# BatteryRegulators.net
KiCad netlist of a schematic drawn in Altium Designer
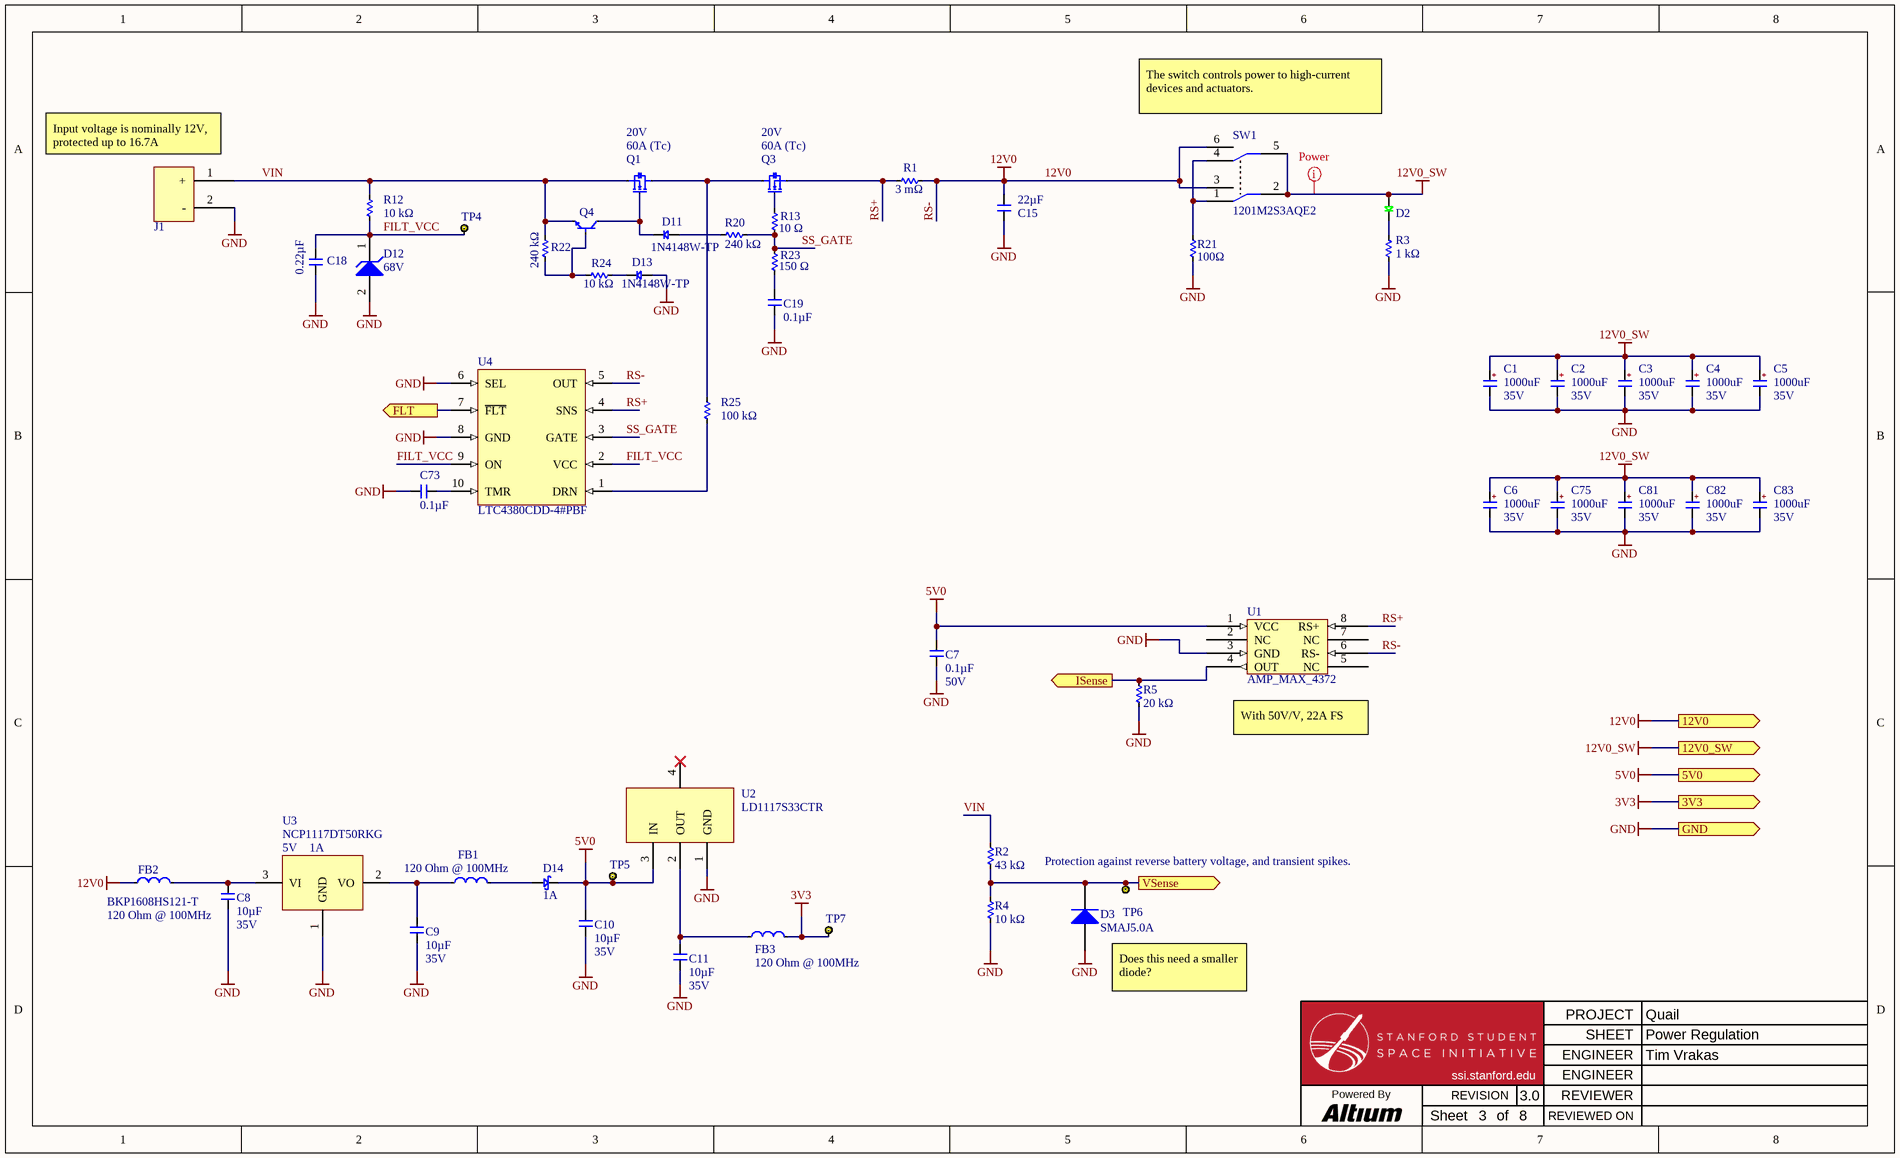
[diagram p0: BatteryRegulators.SchDoc]

(export (version "E")
  (design (tool "Eeschema 10.0.6"))
  (components
    (comp (ref "C1")
      (value "1000uF")
      (footprint "ALUM_CAP_5mm-Leads")
      (description "1000uF (1mF) Electrolytic Capacitor in a 12.5mm x 20mm can package")
      (fields (field (name "RATING") "35V") (field (name "Comment") "CAP_ALUM_1000uF_ECA-1VM102B"))
      (libsource (lib "Stanford Student Space Initiative") (part "CAP_ALUM_1000uF_ECA-1VM102B"))
    )
    (comp (ref "C2")
      (value "1000uF")
      (footprint "ALUM_CAP_5mm-Leads")
      (description "1000uF (1mF) Electrolytic Capacitor in a 12.5mm x 20mm can package")
      (fields (field (name "RATING") "35V") (field (name "Comment") "CAP_ALUM_1000uF_ECA-1VM102B"))
      (libsource (lib "Stanford Student Space Initiative") (part "CAP_ALUM_1000uF_ECA-1VM102B"))
    )
    (comp (ref "C3")
      (value "1000uF")
      (footprint "ALUM_CAP_5mm-Leads")
      (description "1000uF (1mF) Electrolytic Capacitor in a 12.5mm x 20mm can package")
      (fields (field (name "RATING") "35V") (field (name "Comment") "CAP_ALUM_1000uF_ECA-1VM102B"))
      (libsource (lib "Stanford Student Space Initiative") (part "CAP_ALUM_1000uF_ECA-1VM102B"))
    )
    (comp (ref "C4")
      (value "1000uF")
      (footprint "ALUM_CAP_5mm-Leads")
      (description "1000uF (1mF) Electrolytic Capacitor in a 12.5mm x 20mm can package")
      (fields (field (name "RATING") "35V") (field (name "Comment") "CAP_ALUM_1000uF_ECA-1VM102B"))
      (libsource (lib "Stanford Student Space Initiative") (part "CAP_ALUM_1000uF_ECA-1VM102B"))
    )
    (comp (ref "C5")
      (value "1000uF")
      (footprint "ALUM_CAP_5mm-Leads")
      (description "1000uF (1mF) Electrolytic Capacitor in a 12.5mm x 20mm can package")
      (fields (field (name "RATING") "35V") (field (name "Comment") "CAP_ALUM_1000uF_ECA-1VM102B"))
      (libsource (lib "Stanford Student Space Initiative") (part "CAP_ALUM_1000uF_ECA-1VM102B"))
    )
    (comp (ref "C6")
      (value "1000uF")
      (footprint "ALUM_CAP_5mm-Leads")
      (description "1000uF (1mF) Electrolytic Capacitor in a 12.5mm x 20mm can package")
      (fields (field (name "RATING") "35V") (field (name "Comment") "CAP_ALUM_1000uF_ECA-1VM102B"))
      (libsource (lib "Stanford Student Space Initiative") (part "CAP_ALUM_1000uF_ECA-1VM102B"))
    )
    (comp (ref "C7")
      (value "490-1519-1-ND")
      (footprint "C0603")
      (description "CAP CER 0603 0.1µF X7R 50V 10%")
      (fields
        (field (name "CAPACITANCE (SHORTHAND)") "0.1µF")
        (field (name "RATED VOLTAGE") "50V")
        (field (name "MANUFACTURER") "Murata Electronics North America")
      )
      (libsource (lib "Stanford Student Space Initiative") (part "__template_cap"))
    )
    (comp (ref "C8")
      (value "490-13248-1-ND")
      (footprint "C0603")
      (description "CAP CER 10UF 35V X5R 0603 20%")
      (fields
        (field (name "CAPACITANCE (SHORTHAND)") "10µF")
        (field (name "RATED VOLTAGE") "35V")
        (field (name "MANUFACTURER") "Murata Electronics North America")
      )
      (libsource (lib "Stanford Student Space Initiative") (part "__template_cap"))
    )
    (comp (ref "C9")
      (value "490-13248-1-ND")
      (footprint "C0603")
      (description "CAP CER 10UF 35V X5R 0603 20%")
      (fields
        (field (name "CAPACITANCE (SHORTHAND)") "10µF")
        (field (name "RATED VOLTAGE") "35V")
        (field (name "MANUFACTURER") "Murata Electronics North America")
      )
      (libsource (lib "Stanford Student Space Initiative") (part "__template_cap"))
    )
    (comp (ref "C10")
      (value "490-13248-1-ND")
      (footprint "C0603")
      (description "CAP CER 10UF 35V X5R 0603 20%")
      (fields
        (field (name "CAPACITANCE (SHORTHAND)") "10µF")
        (field (name "RATED VOLTAGE") "35V")
        (field (name "MANUFACTURER") "Murata Electronics North America")
      )
      (libsource (lib "Stanford Student Space Initiative") (part "__template_cap"))
    )
    (comp (ref "C11")
      (value "490-13248-1-ND")
      (footprint "C0603")
      (description "CAP CER 10UF 35V X5R 0603 20%")
      (fields
        (field (name "CAPACITANCE (SHORTHAND)") "10µF")
        (field (name "RATED VOLTAGE") "35V")
        (field (name "MANUFACTURER") "Murata Electronics North America")
      )
      (libsource (lib "Stanford Student Space Initiative") (part "__template_cap"))
    )
    (comp (ref "C15")
      (value "1276-7076-1-ND")
      (footprint "C0603")
      (description "CAP CER 22UF 16V X5R 0603 20%")
      (fields
        (field (name "MANUFACTURER") "Samsung Electro-Mechanics")
        (field (name "CAPACITANCE (SHORTHAND)") "22µF")
      )
      (libsource (lib "Stanford Student Space Initiative") (part "__template_cap"))
    )
    (comp (ref "C18")
      (value "490-12546-1-ND")
      (footprint "C0603")
      (description "CAP CER 0603 0.22µF X7R 50V 10%")
      (fields
        (field (name "MANUFACTURER") "Murata Electronics North America")
        (field (name "CAPACITANCE (SHORTHAND)") "0.22µF")
      )
      (libsource (lib "Stanford Student Space Initiative") (part "__template_cap"))
    )
    (comp (ref "C19")
      (value "490-1519-1-ND")
      (footprint "C0603")
      (description "CAP CER 0603 0.1µF X7R 50V 10%")
      (fields
        (field (name "CAPACITANCE (SHORTHAND)") "0.1µF")
        (field (name "MANUFACTURER") "Murata Electronics North America")
      )
      (libsource (lib "Stanford Student Space Initiative") (part "__template_cap"))
    )
    (comp (ref "C73")
      (value "490-1519-1-ND")
      (footprint "C0603")
      (description "CAP CER 0603 0.1µF X7R 50V 10%")
      (fields
        (field (name "CAPACITANCE (SHORTHAND)") "0.1µF")
        (field (name "MANUFACTURER") "Murata Electronics North America")
      )
      (libsource (lib "Stanford Student Space Initiative") (part "__template_cap"))
    )
    (comp (ref "C75")
      (value "1000uF")
      (footprint "ALUM_CAP_5mm-Leads")
      (description "1000uF (1mF) Electrolytic Capacitor in a 12.5mm x 20mm can package")
      (fields (field (name "RATING") "35V") (field (name "Comment") "CAP_ALUM_1000uF_ECA-1VM102B"))
      (libsource (lib "Stanford Student Space Initiative") (part "CAP_ALUM_1000uF_ECA-1VM102B"))
    )
    (comp (ref "C81")
      (value "1000uF")
      (footprint "ALUM_CAP_5mm-Leads")
      (description "1000uF (1mF) Electrolytic Capacitor in a 12.5mm x 20mm can package")
      (fields (field (name "RATING") "35V") (field (name "Comment") "CAP_ALUM_1000uF_ECA-1VM102B"))
      (libsource (lib "Stanford Student Space Initiative") (part "CAP_ALUM_1000uF_ECA-1VM102B"))
    )
    (comp (ref "C82")
      (value "1000uF")
      (footprint "ALUM_CAP_5mm-Leads")
      (description "1000uF (1mF) Electrolytic Capacitor in a 12.5mm x 20mm can package")
      (fields (field (name "RATING") "35V") (field (name "Comment") "CAP_ALUM_1000uF_ECA-1VM102B"))
      (libsource (lib "Stanford Student Space Initiative") (part "CAP_ALUM_1000uF_ECA-1VM102B"))
    )
    (comp (ref "C83")
      (value "1000uF")
      (footprint "ALUM_CAP_5mm-Leads")
      (description "1000uF (1mF) Electrolytic Capacitor in a 12.5mm x 20mm can package")
      (fields (field (name "RATING") "35V") (field (name "Comment") "CAP_ALUM_1000uF_ECA-1VM102B"))
      (libsource (lib "Stanford Student Space Initiative") (part "CAP_ALUM_1000uF_ECA-1VM102B"))
    )
    (comp (ref "D2")
      (value "LED_C503B-GCS-CB0C0781")
      (footprint "LED_TH_5MM")
      (description "LED GREEN CLEAR 5MM ROUND T/H")
      (fields
        (field (name "MANUFACTURER") "Cree")
        (field (name "MANUFACTURER PART NUMBER") "C503B-GCS-CB0C0781")
      )
      (libsource (lib "Stanford Student Space Initiative") (part "LED_C503B-GCS-CB0C0781"))
    )
    (comp (ref "D3")
      (value "SMAJ5.0A")
      (footprint "BOUR-SMA-2_V")
      (description "BOURNS - SMAJ5.0A - TVS Diode, SMAJ Series, Unidirectional, 5 V, 9.2 V, DO-214AC (SMA), 2 Pins")
      (libsource (lib "Stanford Student Space Initiative") (part "D-AK-2"))
    )
    (comp (ref "D11")
      (value "DIODE_1N4148WTPMSTR")
      (footprint "SOD123")
      (description "DIODE SWITCH 100V 150MA SOD123")
      (fields
        (field (name "MANUFACTURER PART NUMBER") "1N4148W-TP")
        (field (name "MANUFACTURER") "Micro Commercial Co")
      )
      (libsource (lib "Stanford Student Space Initiative") (part "Symbol"))
    )
    (comp (ref "D12")
      (value "MMSZ5266BT1G")
      (footprint "ONSC-SOD-123-2-425-04_V")
      (description "DIODE ZENER 68V 500MW SOD123 / Zener Diode Single 68V 5% 230Ohm 500mW 2-Pin SOD-123 T/R")
      (fields (field (name "TOLERANCE") "5%") (field (name "ZENER VOLTAGE") "68V"))
      (libsource (lib "Stanford Student Space Initiative") (part "ONSC-K1A2-2"))
    )
    (comp (ref "D13")
      (value "DIODE_1N4148WTPMSTR")
      (footprint "SOD123")
      (description "DIODE SWITCH 100V 150MA SOD123")
      (fields
        (field (name "MANUFACTURER PART NUMBER") "1N4148W-TP")
        (field (name "MANUFACTURER") "Micro Commercial Co")
      )
      (libsource (lib "Stanford Student Space Initiative") (part "Symbol"))
    )
    (comp (ref "D14")
      (value "Diode_CD214A-B1100LF")
      (footprint "SMA")
      (description "Diode Schottky 100V 1A Surface Mount SMA (DO-214AC)")
      (fields
        (field (name "MANUFACTURER PART NUMBER") "CD214A-B1100LF")
        (field (name "CURRENT - AVERAGE RECTIFIED (IO)") "1A")
        (field (name "MANUFACTURER") "Bourns Inc.")
      )
      (libsource (lib "Stanford Student Space Initiative") (part "Diode_CD214A-B1100LF"))
    )
    (comp (ref "FB1")
      (value "FB_120@100MHz_0603")
      (footprint "C0603")
      (description "FERRITE BEAD 120 OHM @ 100 MHz")
      (fields
        (field (name "MANUFACTURER") "Taiyo Yuden")
        (field (name "MANUFACTURER PART NUMBER") "BKP1608HS121-T")
        (field (name "IMPEDANCE @ FREQUENCY") "120 Ohm @ 100MHz")
      )
      (libsource (lib "Stanford Student Space Initiative") (part "FB_120@100MHz_0603"))
    )
    (comp (ref "FB2")
      (value "FB_120@100MHz_0603")
      (footprint "C0603")
      (description "FERRITE BEAD 120 OHM @ 100 MHz")
      (fields
        (field (name "MANUFACTURER") "Taiyo Yuden")
        (field (name "MANUFACTURER PART NUMBER") "BKP1608HS121-T")
        (field (name "IMPEDANCE @ FREQUENCY") "120 Ohm @ 100MHz")
      )
      (libsource (lib "Stanford Student Space Initiative") (part "FB_120@100MHz_0603"))
    )
    (comp (ref "FB3")
      (value "FB_120@100MHz_0603")
      (footprint "C0603")
      (description "FERRITE BEAD 120 OHM @ 100 MHz")
      (fields
        (field (name "MANUFACTURER") "Taiyo Yuden")
        (field (name "MANUFACTURER PART NUMBER") "BKP1608HS121-T")
        (field (name "IMPEDANCE @ FREQUENCY") "120 Ohm @ 100MHz")
      )
      (libsource (lib "Stanford Student Space Initiative") (part "FB_120@100MHz_0603"))
    )
    (comp (ref "J1")
      (value "XT60PW-M")
      (footprint "XT60PW-M-Footprint-1")
      (description "XT60 Sink, Right Angle")
      (libsource (lib "Stanford Student Space Initiative") (part "XT60PW-M-Symbol-1"))
    )
    (comp (ref "Q1")
      (value "NFET_SIR404DP-T1-GE3CT-ND")
      (footprint "POWERPAK_SO-8_SINGLE")
      (description "MOSFET N-CH 20V 60A POWERPAK1212-8")
      (fields
        (field (name "MANUFACTURER") "Vishay Siliconix")
        (field (name "DRAIN TO SOURCE VOLTAGE (VDSS)") "20V")
        (field (name "CURRENT - CONTINUOUS DRAIN (ID) @ 25°C") "60A (Tc)")
        (field (name "MANUFACTURER PART NUMBER") "SIR404DP-T1-GE3")
      )
      (libsource (lib "") (part "Symbol_1"))
    )
    (comp (ref "Q3")
      (value "NFET_SIR404DP-T1-GE3CT-ND")
      (footprint "POWERPAK_SO-8_SINGLE")
      (description "MOSFET N-CH 20V 60A POWERPAK1212-8")
      (fields
        (field (name "MANUFACTURER") "Vishay Siliconix")
        (field (name "DRAIN TO SOURCE VOLTAGE (VDSS)") "20V")
        (field (name "CURRENT - CONTINUOUS DRAIN (ID) @ 25°C") "60A (Tc)")
        (field (name "MANUFACTURER PART NUMBER") "SIR404DP-T1-GE3")
      )
      (libsource (lib "") (part "Symbol_1"))
    )
    (comp (ref "Q4")
      (value "NPN_MMBT3904-7-F")
      (footprint "3SOT23")
      (description "TRANS NPN 40V 0.2A SMD SOT23-3")
      (fields
        (field (name "MANUFACTURER PART NUMBER") "MMBT3904-7-F")
        (field (name "MANUFACTURER") "Diodes Incorporated")
      )
      (libsource (lib "Stanford Student Space Initiative") (part "NPN_MMBT3904-7-F"))
    )
    (comp (ref "R1")
      (value "TLRP3A20CR003FTDG")
      (footprint "R2512")
      (description "Res Current Sense Metal Strip 2512 0.003 Ohm 1% 2W ±25ppm/°C Molded Emboss T/R")
      (fields (field (name "RESISTANCE (OHMS)") "3 mΩ"))
      (libsource (lib "") (part "Symbol_2"))
    )
    (comp (ref "R2")
      (value "311-43.0KHRCT-ND")
      (footprint "R0603")
      (description "RES SMD 43K OHM 1% 1/10W 0603")
      (fields
        (field (name "MANUFACTURER PART NUMBER") "RC0603FR-0743KL")
        (field (name "TOLERANCE") "±1%")
        (field (name "RESISTANCE") "43 kΩ")
      )
      (libsource (lib "Stanford Student Space Initiative") (part "__template_resistor"))
    )
    (comp (ref "R3")
      (value "311-1.00KHRCT-ND")
      (footprint "R0603")
      (description "RES SMD 1K OHM 1% 1/10W 0603")
      (fields
        (field (name "MANUFACTURER") "Yageo")
        (field (name "TOLERANCE") "±1%")
        (field (name "RESISTANCE") "1 kΩ")
      )
      (libsource (lib "Stanford Student Space Initiative") (part "__template_resistor"))
    )
    (comp (ref "R4")
      (value "311-10.0KHRCT-ND")
      (footprint "R0603")
      (description "RES SMD 10K OHM 1% 1/10W 0603")
      (fields
        (field (name "RESISTANCE") "10 kΩ")
        (field (name "MANUFACTURER PART NUMBER") "RC0603FR-0710KL")
        (field (name "MANUFACTURER") "Yageo")
      )
      (libsource (lib "Stanford Student Space Initiative") (part "__template_resistor"))
    )
    (comp (ref "R5")
      (value "311-20.0KHRCT-ND")
      (footprint "R0603")
      (description "RES SMD 20K OHM 1% 1/10W 0603")
      (fields
        (field (name "RESISTANCE") "20 kΩ")
        (field (name "MANUFACTURER PART NUMBER") "RC0603FR-0720KL")
        (field (name "MANUFACTURER") "Yageo")
      )
      (libsource (lib "Stanford Student Space Initiative") (part "__template_resistor"))
    )
    (comp (ref "R12")
      (value "311-10.0KHRCT-ND")
      (footprint "R0603")
      (description "RES SMD 10K OHM 1% 1/10W 0603")
      (fields
        (field (name "MANUFACTURER") "Yageo")
        (field (name "MANUFACTURER PART NUMBER") "RC0603FR-0710KL")
        (field (name "RESISTANCE") "10 kΩ")
      )
      (libsource (lib "Stanford Student Space Initiative") (part "__template_resistor"))
    )
    (comp (ref "R13")
      (value "311-10.0HRCT-ND")
      (footprint "R0603")
      (description "RES SMD 10 OHM 1% 1/10W 0603")
      (fields
        (field (name "MANUFACTURER") "Yageo")
        (field (name "RESISTANCE") "10 Ω")
        (field (name "MANUFACTURER PART NUMBER") "RC0603FR-0710RL")
      )
      (libsource (lib "Stanford Student Space Initiative") (part "__template_resistor"))
    )
    (comp (ref "R20")
      (value "311-240KHRCT-ND")
      (footprint "R0603")
      (description "RES SMD 240K OHM 1% 1/10W 0603")
      (fields
        (field (name "MANUFACTURER PART NUMBER") "RC0603FR-07240KL")
        (field (name "TOLERANCE") "±1%")
        (field (name "RESISTANCE") "240 kΩ")
      )
      (libsource (lib "Stanford Student Space Initiative") (part "__template_resistor"))
    )
    (comp (ref "R21")
      (value "RC2512JK-7W100RL")
      (footprint "R2512")
      (description "Res Thick Film 2512 100 Ohm 5% 1W ±100ppm/°C Molded SMD SMD Embossed T/R")
      (fields (field (name "TOLERANCE") "5%") (field (name "RESISTANCE") "100Ω"))
      (libsource (lib "Stanford Student Space Initiative") (part "__template_resistor"))
    )
    (comp (ref "R22")
      (value "311-240KHRCT-ND")
      (footprint "R0603")
      (description "RES SMD 240K OHM 1% 1/10W 0603")
      (fields
        (field (name "MANUFACTURER PART NUMBER") "RC0603FR-07240KL")
        (field (name "TOLERANCE") "±1%")
        (field (name "RESISTANCE") "240 kΩ")
      )
      (libsource (lib "Stanford Student Space Initiative") (part "__template_resistor"))
    )
    (comp (ref "R23")
      (value "311-150HRCT-ND")
      (footprint "R0603")
      (description "RES SMD 150 OHM 1% 1/10W 0603")
      (fields
        (field (name "RESISTANCE") "150 Ω")
        (field (name "MANUFACTURER PART NUMBER") "RC0603FR-07150RL")
        (field (name "TOLERANCE") "±1%")
      )
      (libsource (lib "Stanford Student Space Initiative") (part "__template_resistor"))
    )
    (comp (ref "R24")
      (value "311-10.0KHRCT-ND")
      (footprint "R0603")
      (description "RES SMD 10K OHM 1% 1/10W 0603")
      (fields
        (field (name "MANUFACTURER") "Yageo")
        (field (name "MANUFACTURER PART NUMBER") "RC0603FR-0710KL")
        (field (name "RESISTANCE") "10 kΩ")
      )
      (libsource (lib "Stanford Student Space Initiative") (part "__template_resistor"))
    )
    (comp (ref "R25")
      (value "311-100KHRCT-ND")
      (footprint "R0603")
      (description "RES SMD 100K OHM 1% 1/10W 0603")
      (fields
        (field (name "MANUFACTURER") "Yageo")
        (field (name "MANUFACTURER PART NUMBER") "RC0603FR-07100KL")
        (field (name "RESISTANCE") "100 kΩ")
      )
      (libsource (lib "Stanford Student Space Initiative") (part "__template_resistor"))
    )
    (comp (ref "SW1")
      (value "1201M2S3AQE2")
      (footprint "1201M2S3AQE2-Footprint-1")
      (description "Switch Slide ON None ON DPDT Side Slide 6A 250VAC 28VDC PC Pins Bracket Mount/Through Hole")
      (libsource (lib "Stanford Student Space Initiative") (part "SWITCH_DPDT"))
    )
    (comp (ref "TP4")
      (value "TEST_POINT_BLACK_KEYSTONE_5001")
      (footprint "TEST_POINT_BLACK_KEYSTONE_5001-Footprint-1")
      (description "BLACK T/H TEST POINT")
      (fields
        (field (name "MANUFACTURER PART NUMBER") "5001")
        (field (name "MANUFACTURER") "Keystone Electronics")
      )
      (libsource (lib "Stanford Student Space Initiative") (part "TEST_POINT_BLACK_KEYSTONE_5001"))
    )
    (comp (ref "TP5")
      (value "TEST_POINT_BLACK_KEYSTONE_5001")
      (footprint "TEST_POINT_KEYSTONE_5001")
      (description "BLACK T/H TEST POINT")
      (fields
        (field (name "MANUFACTURER PART NUMBER") "5001")
        (field (name "MANUFACTURER") "Keystone Electronics")
      )
      (libsource (lib "Stanford Student Space Initiative") (part "TEST_POINT_BLACK_KEYSTONE_5001"))
    )
    (comp (ref "TP6")
      (value "TEST_POINT_BLACK_KEYSTONE_5001")
      (footprint "TEST_POINT_BLACK_KEYSTONE_5001-Footprint-1")
      (description "BLACK T/H TEST POINT")
      (fields
        (field (name "MANUFACTURER PART NUMBER") "5001")
        (field (name "MANUFACTURER") "Keystone Electronics")
      )
      (libsource (lib "Stanford Student Space Initiative") (part "TEST_POINT_BLACK_KEYSTONE_5001"))
    )
    (comp (ref "TP7")
      (value "TEST_POINT_BLACK_KEYSTONE_5001")
      (footprint "TEST_POINT_KEYSTONE_5001")
      (description "BLACK T/H TEST POINT")
      (fields
        (field (name "MANUFACTURER PART NUMBER") "5001")
        (field (name "MANUFACTURER") "Keystone Electronics")
      )
      (libsource (lib "Stanford Student Space Initiative") (part "TEST_POINT_BLACK_KEYSTONE_5001"))
    )
    (comp (ref "U1")
      (value "AMP_MAX_4372")
      (footprint "8SOIC150")
      (description "Low-Cost, UCSP/SOT23, Micropower, High-Side Current-Sense Amplifier with Voltage")
      (libsource (lib "Stanford Student Space Initiative") (part "AMP_MAX_4372"))
    )
    (comp (ref "U2")
      (value "LDO_LD1117S33CTR")
      (footprint "4SOT223")
      (description "IC VOLTAGE REG 3.3V 800MA SOT223 INDUSTRIAL TEMP")
      (fields
        (field (name "MANUFACTURER") "STMicroelectronics")
        (field (name "MANUFACTURER PART NUMBER") "LD1117S33CTR")
      )
      (libsource (lib "Stanford Student Space Initiative") (part "LDO_LD1117S33CTR"))
    )
    (comp (ref "U3")
      (value "LDO_NCP1117DT50RKG")
      (footprint "DPAK")
      (description "IC REG LDO 5V 1A DPAK")
      (fields
        (field (name "MANUFACTURER") "ON Semiconductor")
        (field (name "MANUFACTURER PART NUMBER") "NCP1117DT50RKG")
        (field (name "VOLTAGE - OUTPUT") "5V")
        (field (name "CURRENT - OUTPUT") "1A")
      )
      (libsource (lib "Stanford Student Space Initiative") (part "LDO_NCP1117DT50RKG"))
    )
    (comp (ref "U4")
      (value "LTC4380CDD-4#PBF")
      (footprint "SON50P300X75_HS-11N")
      (description "Hot-swap Controller, 72V, DFN-10")
      (libsource (lib "Stanford Student Space Initiative") (part "LTC4380CDD-4#PBF-Symbol-1"))
    )
  )
  (nets
    (net (code "1") (name "/FILT_VCC") (class "Default")
      (node (ref "C18") (pin "1") (pintype "passive"))
      (node (ref "D12") (pin "1") (pinfunction "K_1") (pintype "passive"))
      (node (ref "R12") (pin "1") (pinfunction "1_1") (pintype "passive"))
      (node (ref "TP4") (pin "1") (pinfunction "1_1") (pintype "passive"))
      (node (ref "U4") (pin "2") (pinfunction "VCC_2") (pintype "input"))
      (node (ref "U4") (pin "9") (pinfunction "ON_9") (pintype "input"))
    )
    (net (code "2") (name "/FLT") (class "Default")
      (node (ref "U4") (pin "7") (pinfunction "~{FLT}_7") (pintype "input"))
    )
    (net (code "3") (name "/ISense") (class "Default")
      (node (ref "R5") (pin "2") (pinfunction "2_2") (pintype "passive"))
      (node (ref "U1") (pin "4") (pinfunction "OUT_4") (pintype "output"))
    )
    (net (code "4") (name "/RS+") (class "Default")
      (node (ref "Q3") (pin "3") (pinfunction "S_3") (pintype "passive"))
      (node (ref "R1") (pin "1") (pinfunction "1_1") (pintype "passive"))
      (node (ref "U1") (pin "8") (pinfunction "RS+_8") (pintype "input"))
      (node (ref "U4") (pin "4") (pinfunction "SNS_4") (pintype "input"))
    )
    (net (code "5") (name "/SS_GATE") (class "Default")
      (node (ref "R13") (pin "1") (pinfunction "1_1") (pintype "passive"))
      (node (ref "R20") (pin "2") (pinfunction "2_2") (pintype "passive"))
      (node (ref "R23") (pin "2") (pinfunction "2_2") (pintype "passive"))
      (node (ref "U4") (pin "3") (pinfunction "GATE_3") (pintype "input"))
    )
    (net (code "6") (name "/VIN") (class "Default")
      (node (ref "J1") (pin "1") (pinfunction "+_1") (pintype "power_in"))
      (node (ref "Q1") (pin "3") (pinfunction "S_3") (pintype "passive"))
      (node (ref "Q4") (pin "3") (pinfunction "E_3") (pintype "passive"))
      (node (ref "R12") (pin "2") (pinfunction "2_2") (pintype "passive"))
      (node (ref "R2") (pin "2") (pinfunction "2_2") (pintype "passive"))
      (node (ref "R22") (pin "2") (pinfunction "2_2") (pintype "passive"))
    )
    (net (code "7") (name "/VSense") (class "Default")
      (node (ref "D3") (pin "2") (pinfunction "K_2") (pintype "passive"))
      (node (ref "R2") (pin "1") (pinfunction "1_1") (pintype "passive"))
      (node (ref "R4") (pin "2") (pinfunction "2_2") (pintype "passive"))
      (node (ref "TP6") (pin "1") (pinfunction "1_1") (pintype "passive"))
    )
    (net (code "8") (name "3V3") (class "Default")
      (node (ref "FB3") (pin "2") (pinfunction "2_2") (pintype "passive"))
      (node (ref "TP7") (pin "1") (pinfunction "1_1") (pintype "passive"))
    )
    (net (code "9") (name "5V0") (class "Default")
      (node (ref "C10") (pin "1") (pintype "passive"))
      (node (ref "C7") (pin "1") (pintype "passive"))
      (node (ref "D14") (pin "2") (pinfunction "Cathode_2") (pintype "passive"))
      (node (ref "TP5") (pin "1") (pinfunction "1_1") (pintype "passive"))
      (node (ref "U1") (pin "1") (pinfunction "VCC_1") (pintype "input"))
      (node (ref "U2") (pin "3") (pinfunction "IN_3") (pintype "passive"))
    )
    (net (code "10") (name "12V0") (class "Default")
      (node (ref "C15") (pin "1") (pintype "passive"))
      (node (ref "FB2") (pin "1") (pinfunction "1_1") (pintype "passive"))
      (node (ref "R1") (pin "2") (pinfunction "2_2") (pintype "passive"))
      (node (ref "SW1") (pin "3") (pinfunction "3_3") (pintype "passive"))
      (node (ref "SW1") (pin "6") (pinfunction "6_6") (pintype "passive"))
      (node (ref "U1") (pin "6") (pinfunction "RS-_6") (pintype "input"))
      (node (ref "U4") (pin "5") (pinfunction "OUT_5") (pintype "input"))
    )
    (net (code "11") (name "12V0_SW") (class "Default")
      (node (ref "C1") (pin "1") (pinfunction "A_1") (pintype "passive"))
      (node (ref "C2") (pin "1") (pinfunction "A_1") (pintype "passive"))
      (node (ref "C3") (pin "1") (pinfunction "A_1") (pintype "passive"))
      (node (ref "C4") (pin "1") (pinfunction "A_1") (pintype "passive"))
      (node (ref "C5") (pin "1") (pinfunction "A_1") (pintype "passive"))
      (node (ref "C6") (pin "1") (pinfunction "A_1") (pintype "passive"))
      (node (ref "C75") (pin "1") (pinfunction "A_1") (pintype "passive"))
      (node (ref "C81") (pin "1") (pinfunction "A_1") (pintype "passive"))
      (node (ref "C82") (pin "1") (pinfunction "A_1") (pintype "passive"))
      (node (ref "C83") (pin "1") (pinfunction "A_1") (pintype "passive"))
      (node (ref "D2") (pin "1") (pinfunction "A_1") (pintype "passive"))
      (node (ref "SW1") (pin "2") (pinfunction "2_2") (pintype "passive"))
      (node (ref "SW1") (pin "5") (pinfunction "5_5") (pintype "passive"))
    )
    (net (code "12") (name "GND") (class "Default")
      (node (ref "C1") (pin "2") (pinfunction "C_2") (pintype "passive"))
      (node (ref "C10") (pin "2") (pintype "passive"))
      (node (ref "C11") (pin "2") (pintype "passive"))
      (node (ref "C15") (pin "2") (pintype "passive"))
      (node (ref "C18") (pin "2") (pintype "passive"))
      (node (ref "C19") (pin "2") (pintype "passive"))
      (node (ref "C2") (pin "2") (pinfunction "C_2") (pintype "passive"))
      (node (ref "C3") (pin "2") (pinfunction "C_2") (pintype "passive"))
      (node (ref "C4") (pin "2") (pinfunction "C_2") (pintype "passive"))
      (node (ref "C5") (pin "2") (pinfunction "C_2") (pintype "passive"))
      (node (ref "C6") (pin "2") (pinfunction "C_2") (pintype "passive"))
      (node (ref "C7") (pin "2") (pintype "passive"))
      (node (ref "C73") (pin "1") (pintype "passive"))
      (node (ref "C75") (pin "2") (pinfunction "C_2") (pintype "passive"))
      (node (ref "C8") (pin "2") (pintype "passive"))
      (node (ref "C81") (pin "2") (pinfunction "C_2") (pintype "passive"))
      (node (ref "C82") (pin "2") (pinfunction "C_2") (pintype "passive"))
      (node (ref "C83") (pin "2") (pinfunction "C_2") (pintype "passive"))
      (node (ref "C9") (pin "2") (pintype "passive"))
      (node (ref "D12") (pin "2") (pinfunction "A_2") (pintype "passive"))
      (node (ref "D13") (pin "1") (pintype "passive"))
      (node (ref "D3") (pin "1") (pinfunction "A_1") (pintype "passive"))
      (node (ref "J1") (pin "2") (pinfunction "-_2") (pintype "power_in"))
      (node (ref "R21") (pin "1") (pinfunction "1_1") (pintype "passive"))
      (node (ref "R3") (pin "1") (pinfunction "1_1") (pintype "passive"))
      (node (ref "R4") (pin "1") (pinfunction "1_1") (pintype "passive"))
      (node (ref "R5") (pin "1") (pinfunction "1_1") (pintype "passive"))
      (node (ref "U1") (pin "3") (pinfunction "GND_3") (pintype "input"))
      (node (ref "U2") (pin "1") (pinfunction "GND_1") (pintype "passive"))
      (node (ref "U3") (pin "1") (pinfunction "GND_1") (pintype "passive"))
      (node (ref "U4") (pin "6") (pinfunction "SEL_6") (pintype "input"))
      (node (ref "U4") (pin "8") (pinfunction "GND_8") (pintype "input"))
    )
    (net (code "13") (name "Net-(C19-Pad1)") (class "Default")
      (node (ref "C19") (pin "1") (pintype "passive"))
      (node (ref "R23") (pin "1") (pinfunction "1_1") (pintype "passive"))
    )
    (net (code "14") (name "Net-(D2-K)") (class "Default")
      (node (ref "D2") (pin "2") (pinfunction "K_2") (pintype "passive"))
      (node (ref "R3") (pin "2") (pinfunction "2_2") (pintype "passive"))
    )
    (net (code "15") (name "Net-(D11-Pad1)") (class "Default")
      (node (ref "D11") (pin "1") (pintype "passive"))
      (node (ref "R20") (pin "1") (pinfunction "1_1") (pintype "passive"))
    )
    (net (code "16") (name "Net-(D13-Pad2)") (class "Default")
      (node (ref "D13") (pin "2") (pintype "passive"))
      (node (ref "R24") (pin "1") (pinfunction "1_1") (pintype "passive"))
    )
    (net (code "17") (name "Net-(D14-Anode)") (class "Default")
      (node (ref "D14") (pin "1") (pinfunction "Anode_1") (pintype "passive"))
      (node (ref "FB1") (pin "2") (pinfunction "2_2") (pintype "passive"))
    )
    (net (code "18") (name "Net-(Q1-D)") (class "Default")
      (node (ref "Q1") (pin "1") (pinfunction "D_1") (pintype "passive"))
      (node (ref "Q3") (pin "1") (pinfunction "D_1") (pintype "passive"))
      (node (ref "R25") (pin "2") (pinfunction "2_2") (pintype "passive"))
    )
    (net (code "19") (name "Net-(Q1-G)") (class "Default")
      (node (ref "D11") (pin "2") (pintype "passive"))
      (node (ref "Q1") (pin "2") (pinfunction "G_2") (pintype "passive"))
      (node (ref "Q4") (pin "2") (pinfunction "C_2") (pintype "passive"))
    )
    (net (code "20") (name "Net-(Q3-G)") (class "Default")
      (node (ref "Q3") (pin "2") (pinfunction "G_2") (pintype "passive"))
      (node (ref "R13") (pin "2") (pinfunction "2_2") (pintype "passive"))
    )
    (net (code "21") (name "Net-(Q4-B)") (class "Default")
      (node (ref "Q4") (pin "1") (pinfunction "B_1") (pintype "passive"))
      (node (ref "R22") (pin "1") (pinfunction "1_1") (pintype "passive"))
      (node (ref "R24") (pin "2") (pinfunction "2_2") (pintype "passive"))
    )
    (net (code "22") (name "Net-(R21-Pad2)") (class "Default")
      (node (ref "R21") (pin "2") (pinfunction "2_2") (pintype "passive"))
      (node (ref "SW1") (pin "1") (pinfunction "1_1") (pintype "passive"))
      (node (ref "SW1") (pin "4") (pinfunction "4_4") (pintype "passive"))
    )
    (net (code "23") (name "Net-(U2-OUT)") (class "Default")
      (node (ref "C11") (pin "1") (pintype "passive"))
      (node (ref "FB3") (pin "1") (pinfunction "1_1") (pintype "passive"))
      (node (ref "U2") (pin "2") (pinfunction "OUT_2") (pintype "passive"))
    )
    (net (code "24") (name "Net-(U3-VI)") (class "Default")
      (node (ref "C8") (pin "1") (pintype "passive"))
      (node (ref "FB2") (pin "2") (pinfunction "2_2") (pintype "passive"))
      (node (ref "U3") (pin "3") (pinfunction "VI_3") (pintype "passive"))
    )
    (net (code "25") (name "Net-(U3-VO)") (class "Default")
      (node (ref "C9") (pin "1") (pintype "passive"))
      (node (ref "FB1") (pin "1") (pinfunction "1_1") (pintype "passive"))
      (node (ref "U3") (pin "2") (pinfunction "VO_2") (pintype "passive"))
    )
    (net (code "26") (name "Net-(U4-DRN)") (class "Default")
      (node (ref "R25") (pin "1") (pinfunction "1_1") (pintype "passive"))
      (node (ref "U4") (pin "1") (pinfunction "DRN_1") (pintype "input"))
    )
    (net (code "27") (name "Net-(U4-TMR)") (class "Default")
      (node (ref "C73") (pin "2") (pintype "passive"))
      (node (ref "U4") (pin "10") (pinfunction "TMR_10") (pintype "input"))
    )
    (net (code "28") (name "unconnected-(U1-NC-Pad2)") (class "Default")
      (node (ref "U1") (pin "2") (pinfunction "NC_2") (pintype "tri_state"))
    )
    (net (code "29") (name "unconnected-(U1-NC-Pad5)") (class "Default")
      (node (ref "U1") (pin "5") (pinfunction "NC_5") (pintype "tri_state"))
    )
    (net (code "30") (name "unconnected-(U1-NC-Pad7)") (class "Default")
      (node (ref "U1") (pin "7") (pinfunction "NC_7") (pintype "tri_state"))
    )
    (net (code "31") (name "unconnected-(U2-GND-Pad4)") (class "Default")
      (node (ref "U2") (pin "4") (pinfunction "GND_4") (pintype "passive+no_connect"))
    )
  )
)
